# so16.net
KiCad netlist of a schematic drawn in EAGLE
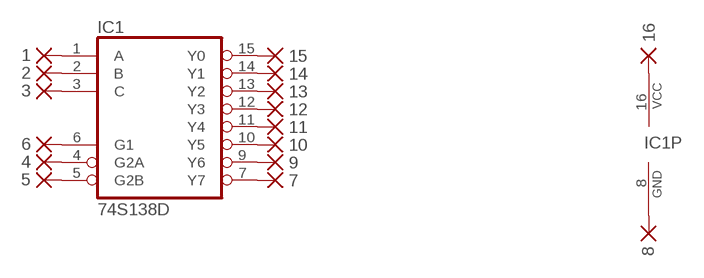
[diagram p0: schematic, sheet 1]

(export (version "E")
  (design (tool "Eeschema 10.0.6"))
  (components
    (comp (ref "1")
      (value "PAD-0360")
      (footprint "eagle-import:0360")
      (libsource (lib "eagle-import") (part "PAD-0360"))
    )
    (comp (ref "2")
      (value "PAD-0360")
      (footprint "eagle-import:0360")
      (libsource (lib "eagle-import") (part "PAD-0360"))
    )
    (comp (ref "3")
      (value "PAD-0360")
      (footprint "eagle-import:0360")
      (libsource (lib "eagle-import") (part "PAD-0360"))
    )
    (comp (ref "4")
      (value "PAD-0360")
      (footprint "eagle-import:0360")
      (libsource (lib "eagle-import") (part "PAD-0360"))
    )
    (comp (ref "5")
      (value "PAD-0360")
      (footprint "eagle-import:0360")
      (libsource (lib "eagle-import") (part "PAD-0360"))
    )
    (comp (ref "6")
      (value "PAD-0360")
      (footprint "eagle-import:0360")
      (libsource (lib "eagle-import") (part "PAD-0360"))
    )
    (comp (ref "7")
      (value "PAD-0360")
      (footprint "eagle-import:0360")
      (libsource (lib "eagle-import") (part "PAD-0360"))
    )
    (comp (ref "8")
      (value "PAD-0360")
      (footprint "eagle-import:0360")
      (libsource (lib "eagle-import") (part "PAD-0360"))
    )
    (comp (ref "9")
      (value "PAD-0360")
      (footprint "eagle-import:0360")
      (libsource (lib "eagle-import") (part "PAD-0360"))
    )
    (comp (ref "10")
      (value "PAD-0360")
      (footprint "eagle-import:0360")
      (libsource (lib "eagle-import") (part "PAD-0360"))
    )
    (comp (ref "11")
      (value "PAD-0360")
      (footprint "eagle-import:0360")
      (libsource (lib "eagle-import") (part "PAD-0360"))
    )
    (comp (ref "12")
      (value "PAD-0360")
      (footprint "eagle-import:0360")
      (libsource (lib "eagle-import") (part "PAD-0360"))
    )
    (comp (ref "13")
      (value "PAD-0360")
      (footprint "eagle-import:0360")
      (libsource (lib "eagle-import") (part "PAD-0360"))
    )
    (comp (ref "14")
      (value "PAD-0360")
      (footprint "eagle-import:0360")
      (libsource (lib "eagle-import") (part "PAD-0360"))
    )
    (comp (ref "15")
      (value "PAD-0360")
      (footprint "eagle-import:0360")
      (libsource (lib "eagle-import") (part "PAD-0360"))
    )
    (comp (ref "16")
      (value "PAD-0360")
      (footprint "eagle-import:0360")
      (libsource (lib "eagle-import") (part "PAD-0360"))
    )
    (comp (ref "IC1")
      (value "74S138D")
      (footprint "eagle-import:SO16")
      (libsource (lib "eagle-import") (part "74138DS"))
    )
  )
  (nets
    (net (code "1") (name "Net-(1-P)") (class "Default")
      (node (ref "1") (pin "P$1") (pinfunction "P_P$1") (pintype "passive"))
      (node (ref "IC1") (pin "1") (pinfunction "A_1") (pintype "input"))
    )
    (net (code "2") (name "Net-(2-P)") (class "Default")
      (node (ref "2") (pin "P$1") (pinfunction "P_P$1") (pintype "passive"))
      (node (ref "IC1") (pin "2") (pinfunction "B_2") (pintype "input"))
    )
    (net (code "3") (name "Net-(3-P)") (class "Default")
      (node (ref "3") (pin "P$1") (pinfunction "P_P$1") (pintype "passive"))
      (node (ref "IC1") (pin "3") (pinfunction "C_3") (pintype "input"))
    )
    (net (code "4") (name "Net-(4-P)") (class "Default")
      (node (ref "4") (pin "P$1") (pinfunction "P_P$1") (pintype "passive"))
      (node (ref "IC1") (pin "4") (pinfunction "G2A_4") (pintype "input"))
    )
    (net (code "5") (name "Net-(5-P)") (class "Default")
      (node (ref "5") (pin "P$1") (pinfunction "P_P$1") (pintype "passive"))
      (node (ref "IC1") (pin "5") (pinfunction "G2B_5") (pintype "input"))
    )
    (net (code "6") (name "Net-(6-P)") (class "Default")
      (node (ref "6") (pin "P$1") (pinfunction "P_P$1") (pintype "passive"))
      (node (ref "IC1") (pin "6") (pinfunction "G1_6") (pintype "input"))
    )
    (net (code "7") (name "Net-(7-P)") (class "Default")
      (node (ref "7") (pin "P$1") (pinfunction "P_P$1") (pintype "passive"))
      (node (ref "IC1") (pin "7") (pinfunction "Y7_7") (pintype "output"))
    )
    (net (code "8") (name "Net-(8-P)") (class "Default")
      (node (ref "8") (pin "P$1") (pinfunction "P_P$1") (pintype "passive"))
      (node (ref "IC1") (pin "8") (pinfunction "GND_8") (pintype "power_in"))
    )
    (net (code "9") (name "Net-(9-P)") (class "Default")
      (node (ref "9") (pin "P$1") (pinfunction "P_P$1") (pintype "passive"))
      (node (ref "IC1") (pin "9") (pinfunction "Y6_9") (pintype "output"))
    )
    (net (code "10") (name "Net-(10-P)") (class "Default")
      (node (ref "10") (pin "P$1") (pinfunction "P_P$1") (pintype "passive"))
      (node (ref "IC1") (pin "10") (pinfunction "Y5_10") (pintype "output"))
    )
    (net (code "11") (name "Net-(11-P)") (class "Default")
      (node (ref "11") (pin "P$1") (pinfunction "P_P$1") (pintype "passive"))
      (node (ref "IC1") (pin "11") (pinfunction "Y4_11") (pintype "output"))
    )
    (net (code "12") (name "Net-(12-P)") (class "Default")
      (node (ref "12") (pin "P$1") (pinfunction "P_P$1") (pintype "passive"))
      (node (ref "IC1") (pin "12") (pinfunction "Y3_12") (pintype "output"))
    )
    (net (code "13") (name "Net-(13-P)") (class "Default")
      (node (ref "13") (pin "P$1") (pinfunction "P_P$1") (pintype "passive"))
      (node (ref "IC1") (pin "13") (pinfunction "Y2_13") (pintype "output"))
    )
    (net (code "14") (name "Net-(14-P)") (class "Default")
      (node (ref "14") (pin "P$1") (pinfunction "P_P$1") (pintype "passive"))
      (node (ref "IC1") (pin "14") (pinfunction "Y1_14") (pintype "output"))
    )
    (net (code "15") (name "Net-(15-P)") (class "Default")
      (node (ref "15") (pin "P$1") (pinfunction "P_P$1") (pintype "passive"))
      (node (ref "IC1") (pin "15") (pinfunction "Y0_15") (pintype "output"))
    )
    (net (code "16") (name "Net-(16-P)") (class "Default")
      (node (ref "16") (pin "P$1") (pinfunction "P_P$1") (pintype "passive"))
      (node (ref "IC1") (pin "16") (pinfunction "VCC_16") (pintype "power_in"))
    )
  )
)
